# Grove_RTD_Sensor.net
KiCad netlist of a schematic drawn in EAGLE
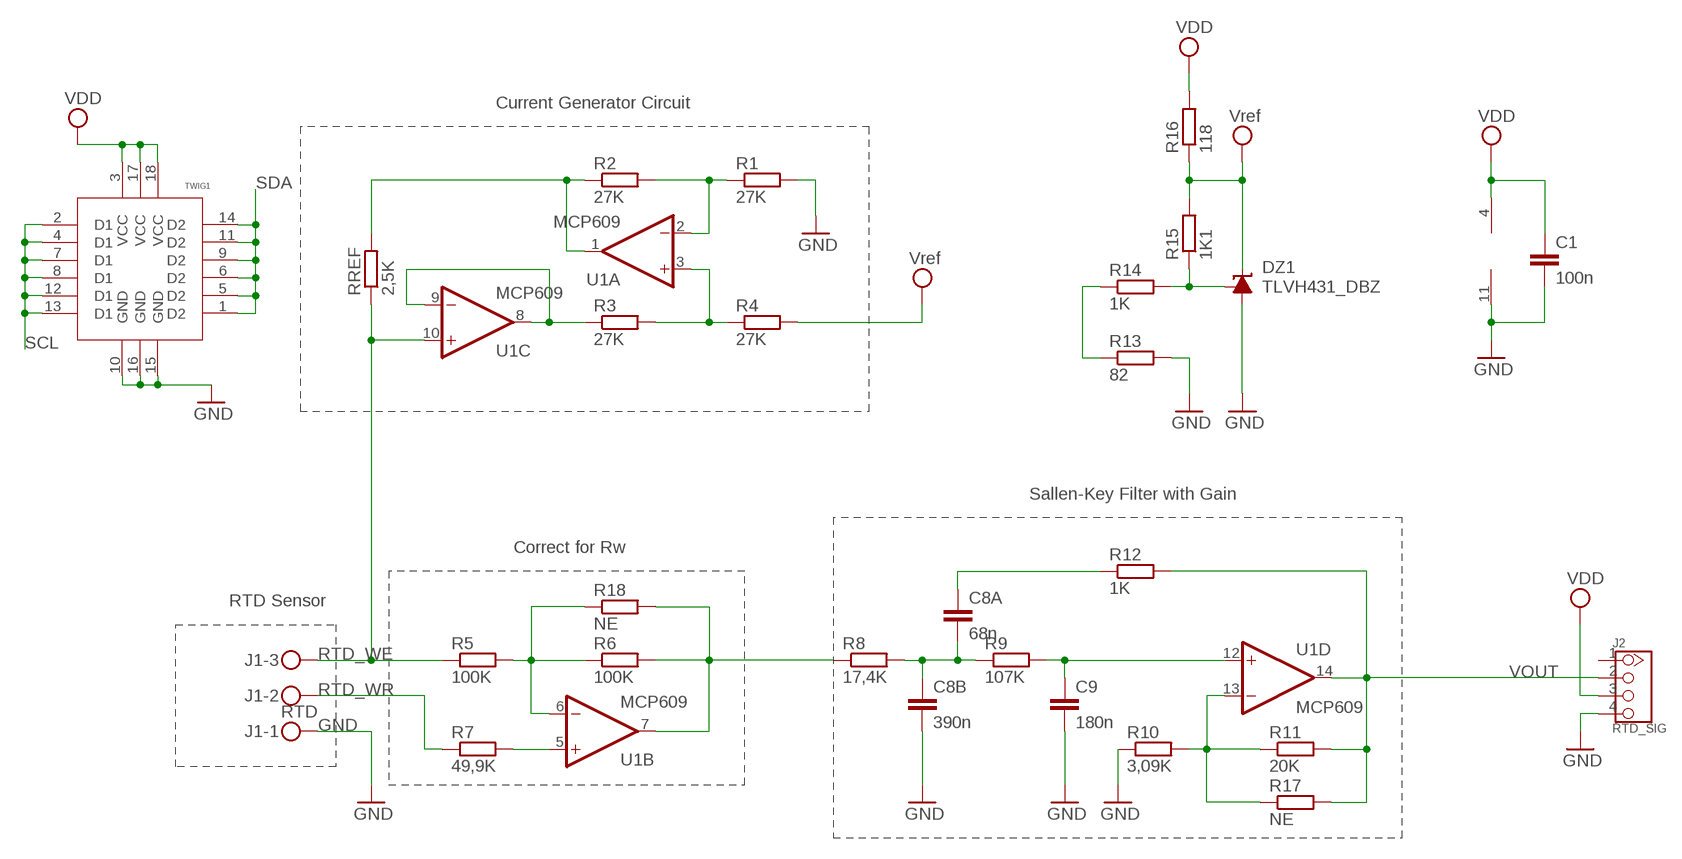
[diagram p0: schematic, sheet 1]

(export (version "E")
  (design (tool "Eeschema 10.0.6"))
  (components
    (comp (ref "C1")
      (value "100n")
      (footprint "eagle-import:C0805")
      (libsource (lib "eagle-import") (part "C-EUC0805"))
    )
    (comp (ref "C8A")
      (value "68n")
      (footprint "eagle-import:C0805")
      (libsource (lib "eagle-import") (part "C-EUC0805"))
    )
    (comp (ref "C8B")
      (value "390n")
      (footprint "eagle-import:C0805")
      (libsource (lib "eagle-import") (part "C-EUC0805"))
    )
    (comp (ref "C9")
      (value "180n")
      (footprint "eagle-import:C0805")
      (libsource (lib "eagle-import") (part "C-EUC0805"))
    )
    (comp (ref "DZ1")
      (value "TLVH431_DBZ")
      (footprint "eagle-import:SOT23")
      (libsource (lib "eagle-import") (part "TLVH431_DBZ"))
    )
    (comp (ref "J1")
      (value "RTD")
      (footprint "eagle-import:MKDSN1,5_3-5,08")
      (libsource (lib "eagle-import") (part "MKDSN1,5/3-5,08"))
    )
    (comp (ref "J2")
      (value "RTD_SIG")
      (footprint "eagle-import:2.0_1X4")
      (libsource (lib "eagle-import") (part "TWIG_2.0-DIP-FEMALE"))
    )
    (comp (ref "R1")
      (value "27K")
      (footprint "eagle-import:R0805")
      (libsource (lib "eagle-import") (part "R-EU_R0805"))
    )
    (comp (ref "R2")
      (value "27K")
      (footprint "eagle-import:R0805")
      (libsource (lib "eagle-import") (part "R-EU_R0805"))
    )
    (comp (ref "R3")
      (value "27K")
      (footprint "eagle-import:R0805")
      (libsource (lib "eagle-import") (part "R-EU_R0805"))
    )
    (comp (ref "R4")
      (value "27K")
      (footprint "eagle-import:R0805")
      (libsource (lib "eagle-import") (part "R-EU_R0805"))
    )
    (comp (ref "R5")
      (value "100K")
      (footprint "eagle-import:R0805")
      (libsource (lib "eagle-import") (part "R-EU_R0805"))
    )
    (comp (ref "R6")
      (value "100K")
      (footprint "eagle-import:R0805")
      (libsource (lib "eagle-import") (part "R-EU_R0805"))
    )
    (comp (ref "R7")
      (value "49,9K")
      (footprint "eagle-import:R0805")
      (libsource (lib "eagle-import") (part "R-EU_R0805"))
    )
    (comp (ref "R8")
      (value "17,4K")
      (footprint "eagle-import:R0805")
      (libsource (lib "eagle-import") (part "R-EU_R0805"))
    )
    (comp (ref "R9")
      (value "107K")
      (footprint "eagle-import:R0805")
      (libsource (lib "eagle-import") (part "R-EU_R0805"))
    )
    (comp (ref "R10")
      (value "3,09K")
      (footprint "eagle-import:R0805")
      (libsource (lib "eagle-import") (part "R-EU_R0805"))
    )
    (comp (ref "R11")
      (value "20K")
      (footprint "eagle-import:R0805")
      (libsource (lib "eagle-import") (part "R-EU_R0805"))
    )
    (comp (ref "R12")
      (value "1K")
      (footprint "eagle-import:R0805")
      (libsource (lib "eagle-import") (part "R-EU_R0805"))
    )
    (comp (ref "R13")
      (value "82")
      (footprint "eagle-import:R0805")
      (libsource (lib "eagle-import") (part "R-EU_R0805"))
    )
    (comp (ref "R14")
      (value "1K")
      (footprint "eagle-import:R0805")
      (libsource (lib "eagle-import") (part "R-EU_R0805"))
    )
    (comp (ref "R15")
      (value "1K1")
      (footprint "eagle-import:R0805")
      (libsource (lib "eagle-import") (part "R-EU_R0805"))
    )
    (comp (ref "R16")
      (value "118")
      (footprint "eagle-import:R0805")
      (libsource (lib "eagle-import") (part "R-EU_R0805"))
    )
    (comp (ref "R17")
      (value "NE")
      (footprint "eagle-import:R0805")
      (libsource (lib "eagle-import") (part "R-EU_R0805"))
    )
    (comp (ref "R18")
      (value "NE")
      (footprint "eagle-import:R0805")
      (libsource (lib "eagle-import") (part "R-EU_R0805"))
    )
    (comp (ref "RREF")
      (value "2,5K")
      (footprint "eagle-import:R0805")
      (libsource (lib "eagle-import") (part "R-EU_R0805"))
    )
    (comp (ref "TWIG1")
      (value "TWIG-U2'HOLES'")
      (footprint "eagle-import:U2_HOLES")
      (libsource (lib "eagle-import") (part "TWIG-U2'HOLES'"))
    )
    (comp (ref "U1")
      (value "MCP609")
      (footprint "eagle-import:SO14")
      (libsource (lib "eagle-import") (part "MCP609"))
    )
  )
  (nets
    (net (code "1") (name "/RTD_WE") (class "Default")
      (node (ref "J1") (pin "3") (pinfunction "KL_3") (pintype "passive"))
      (node (ref "R5") (pin "1") (pinfunction "1_1") (pintype "passive"))
      (node (ref "RREF") (pin "1") (pinfunction "1_1") (pintype "passive"))
      (node (ref "U1") (pin "10") (pinfunction "+IN_10") (pintype "input"))
    )
    (net (code "2") (name "/RTD_WR") (class "Default")
      (node (ref "J1") (pin "2") (pinfunction "KL_2") (pintype "passive"))
      (node (ref "R7") (pin "1") (pinfunction "1_1") (pintype "passive"))
    )
    (net (code "3") (name "/SCL") (class "Default")
      (node (ref "TWIG1") (pin "12") (pinfunction "D1_12") (pintype "bidirectional"))
      (node (ref "TWIG1") (pin "13") (pinfunction "D1_13") (pintype "bidirectional"))
      (node (ref "TWIG1") (pin "2") (pinfunction "D1_2") (pintype "bidirectional"))
      (node (ref "TWIG1") (pin "4") (pinfunction "D1_4") (pintype "bidirectional"))
      (node (ref "TWIG1") (pin "7") (pinfunction "D1_7") (pintype "bidirectional"))
      (node (ref "TWIG1") (pin "8") (pinfunction "D1_8") (pintype "bidirectional"))
    )
    (net (code "4") (name "/SDA") (class "Default")
      (node (ref "TWIG1") (pin "1") (pinfunction "D2_1") (pintype "bidirectional"))
      (node (ref "TWIG1") (pin "11") (pinfunction "D2_11") (pintype "bidirectional"))
      (node (ref "TWIG1") (pin "14") (pinfunction "D2_14") (pintype "bidirectional"))
      (node (ref "TWIG1") (pin "5") (pinfunction "D2_5") (pintype "bidirectional"))
      (node (ref "TWIG1") (pin "6") (pinfunction "D2_6") (pintype "bidirectional"))
      (node (ref "TWIG1") (pin "9") (pinfunction "D2_9") (pintype "bidirectional"))
    )
    (net (code "5") (name "/VOUT") (class "Default")
      (node (ref "J2") (pin "2") (pinfunction "2_2") (pintype "bidirectional"))
      (node (ref "R11") (pin "2") (pinfunction "2_2") (pintype "passive"))
      (node (ref "R12") (pin "2") (pinfunction "2_2") (pintype "passive"))
      (node (ref "R17") (pin "2") (pinfunction "2_2") (pintype "passive"))
      (node (ref "U1") (pin "14") (pinfunction "OUT_14") (pintype "output"))
    )
    (net (code "6") (name "GND") (class "Default")
      (node (ref "C1") (pin "2") (pinfunction "2_2") (pintype "passive"))
      (node (ref "C8B") (pin "2") (pinfunction "2_2") (pintype "passive"))
      (node (ref "C9") (pin "2") (pinfunction "2_2") (pintype "passive"))
      (node (ref "DZ1") (pin "3") (pinfunction "A_3") (pintype "passive"))
      (node (ref "J1") (pin "1") (pinfunction "KL_1") (pintype "passive"))
      (node (ref "J2") (pin "4") (pinfunction "4_4") (pintype "bidirectional"))
      (node (ref "R1") (pin "2") (pinfunction "2_2") (pintype "passive"))
      (node (ref "R10") (pin "1") (pinfunction "1_1") (pintype "passive"))
      (node (ref "R13") (pin "2") (pinfunction "2_2") (pintype "passive"))
      (node (ref "TWIG1") (pin "10") (pinfunction "GND_10") (pintype "power_in"))
      (node (ref "TWIG1") (pin "15") (pinfunction "GND_15") (pintype "power_in"))
      (node (ref "TWIG1") (pin "16") (pinfunction "GND_16") (pintype "power_in"))
      (node (ref "U1") (pin "11") (pinfunction "V-_11") (pintype "power_in"))
    )
    (net (code "7") (name "Net-(C8A-Pad1)") (class "Default")
      (node (ref "C8A") (pin "1") (pinfunction "1_1") (pintype "passive"))
      (node (ref "R12") (pin "1") (pinfunction "1_1") (pintype "passive"))
    )
    (net (code "8") (name "Net-(C8A-Pad2)") (class "Default")
      (node (ref "C8A") (pin "2") (pinfunction "2_2") (pintype "passive"))
      (node (ref "C8B") (pin "1") (pinfunction "1_1") (pintype "passive"))
      (node (ref "R8") (pin "2") (pinfunction "2_2") (pintype "passive"))
      (node (ref "R9") (pin "1") (pinfunction "1_1") (pintype "passive"))
    )
    (net (code "9") (name "Net-(DZ1-FB)") (class "Default")
      (node (ref "DZ1") (pin "1") (pinfunction "FB_1") (pintype "passive"))
      (node (ref "R14") (pin "2") (pinfunction "2_2") (pintype "passive"))
      (node (ref "R15") (pin "1") (pinfunction "1_1") (pintype "passive"))
    )
    (net (code "10") (name "Net-(R13-Pad1)") (class "Default")
      (node (ref "R13") (pin "1") (pinfunction "1_1") (pintype "passive"))
      (node (ref "R14") (pin "1") (pinfunction "1_1") (pintype "passive"))
    )
    (net (code "11") (name "Net-(U1A-+IN)") (class "Default")
      (node (ref "R3") (pin "2") (pinfunction "2_2") (pintype "passive"))
      (node (ref "R4") (pin "1") (pinfunction "1_1") (pintype "passive"))
      (node (ref "U1") (pin "3") (pinfunction "+IN_3") (pintype "input"))
    )
    (net (code "12") (name "Net-(U1A--IN)") (class "Default")
      (node (ref "R1") (pin "1") (pinfunction "1_1") (pintype "passive"))
      (node (ref "R2") (pin "2") (pinfunction "2_2") (pintype "passive"))
      (node (ref "U1") (pin "2") (pinfunction "-IN_2") (pintype "input"))
    )
    (net (code "13") (name "Net-(U1A-OUT)") (class "Default")
      (node (ref "R2") (pin "1") (pinfunction "1_1") (pintype "passive"))
      (node (ref "RREF") (pin "2") (pinfunction "2_2") (pintype "passive"))
      (node (ref "U1") (pin "1") (pinfunction "OUT_1") (pintype "output"))
    )
    (net (code "14") (name "Net-(U1B-+IN)") (class "Default")
      (node (ref "R7") (pin "2") (pinfunction "2_2") (pintype "passive"))
      (node (ref "U1") (pin "5") (pinfunction "+IN_5") (pintype "input"))
    )
    (net (code "15") (name "Net-(U1B--IN)") (class "Default")
      (node (ref "R18") (pin "1") (pinfunction "1_1") (pintype "passive"))
      (node (ref "R5") (pin "2") (pinfunction "2_2") (pintype "passive"))
      (node (ref "R6") (pin "1") (pinfunction "1_1") (pintype "passive"))
      (node (ref "U1") (pin "6") (pinfunction "-IN_6") (pintype "input"))
    )
    (net (code "16") (name "Net-(U1B-OUT)") (class "Default")
      (node (ref "R18") (pin "2") (pinfunction "2_2") (pintype "passive"))
      (node (ref "R6") (pin "2") (pinfunction "2_2") (pintype "passive"))
      (node (ref "R8") (pin "1") (pinfunction "1_1") (pintype "passive"))
      (node (ref "U1") (pin "7") (pinfunction "OUT_7") (pintype "output"))
    )
    (net (code "17") (name "Net-(U1C--IN)") (class "Default")
      (node (ref "R3") (pin "1") (pinfunction "1_1") (pintype "passive"))
      (node (ref "U1") (pin "8") (pinfunction "OUT_8") (pintype "output"))
      (node (ref "U1") (pin "9") (pinfunction "-IN_9") (pintype "input"))
    )
    (net (code "18") (name "Net-(U1D-+IN)") (class "Default")
      (node (ref "C9") (pin "1") (pinfunction "1_1") (pintype "passive"))
      (node (ref "R9") (pin "2") (pinfunction "2_2") (pintype "passive"))
      (node (ref "U1") (pin "12") (pinfunction "+IN_12") (pintype "input"))
    )
    (net (code "19") (name "Net-(U1D--IN)") (class "Default")
      (node (ref "R10") (pin "2") (pinfunction "2_2") (pintype "passive"))
      (node (ref "R11") (pin "1") (pinfunction "1_1") (pintype "passive"))
      (node (ref "R17") (pin "1") (pinfunction "1_1") (pintype "passive"))
      (node (ref "U1") (pin "13") (pinfunction "-IN_13") (pintype "input"))
    )
    (net (code "20") (name "VDD") (class "Default")
      (node (ref "C1") (pin "1") (pinfunction "1_1") (pintype "passive"))
      (node (ref "J2") (pin "3") (pinfunction "3_3") (pintype "bidirectional"))
      (node (ref "R16") (pin "2") (pinfunction "2_2") (pintype "passive"))
      (node (ref "TWIG1") (pin "17") (pinfunction "VCC_17") (pintype "power_in"))
      (node (ref "TWIG1") (pin "18") (pinfunction "VCC_18") (pintype "power_in"))
      (node (ref "TWIG1") (pin "3") (pinfunction "VCC_3") (pintype "power_in"))
      (node (ref "U1") (pin "4") (pinfunction "V+_4") (pintype "power_in"))
    )
    (net (code "21") (name "Vref") (class "Default")
      (node (ref "DZ1") (pin "2") (pinfunction "C_2") (pintype "passive"))
      (node (ref "R15") (pin "2") (pinfunction "2_2") (pintype "passive"))
      (node (ref "R16") (pin "1") (pinfunction "1_1") (pintype "passive"))
      (node (ref "R4") (pin "2") (pinfunction "2_2") (pintype "passive"))
    )
    (net (code "22") (name "unconnected-(J2-Pad1)") (class "Default")
      (node (ref "J2") (pin "1") (pinfunction "1_1") (pintype "bidirectional"))
    )
  )
)
